# UmnitsaUltrasonic.net
KiCad netlist of a schematic drawn in EAGLE
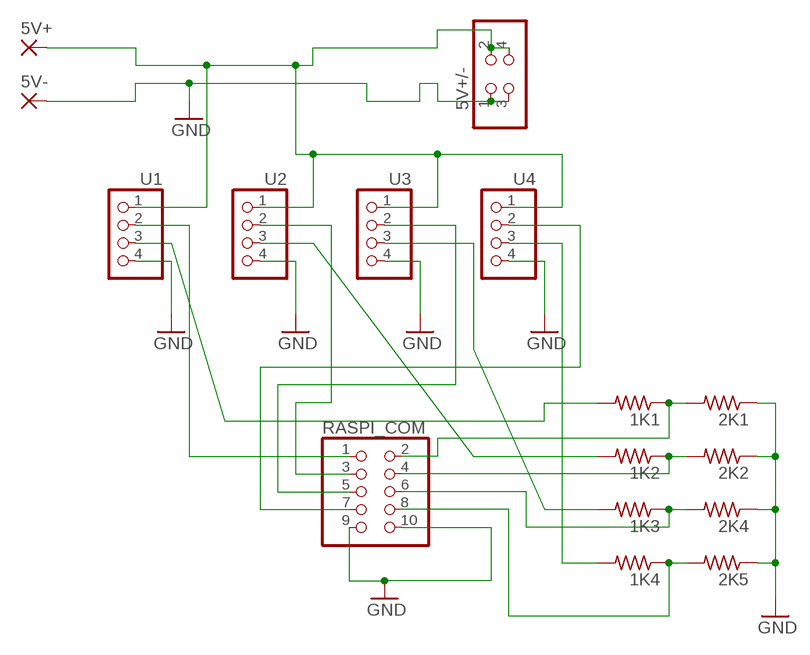
[diagram p0: schematic, sheet 1]

(export (version "E")
  (design (tool "Eeschema 10.0.6"))
  (components
    (comp (ref "1K1")
      (value "R-US_0204/7")
      (footprint "eagle-import:0204_7")
      (libsource (lib "eagle-import") (part "R-US_0204/7"))
    )
    (comp (ref "1K2")
      (value "R-US_0204/7")
      (footprint "eagle-import:0204_7")
      (libsource (lib "eagle-import") (part "R-US_0204/7"))
    )
    (comp (ref "1K3")
      (value "R-US_0204/7")
      (footprint "eagle-import:0204_7")
      (libsource (lib "eagle-import") (part "R-US_0204/7"))
    )
    (comp (ref "1K4")
      (value "R-US_0204/7")
      (footprint "eagle-import:0204_7")
      (libsource (lib "eagle-import") (part "R-US_0204/7"))
    )
    (comp (ref "2K1")
      (value "R-US_0204/7")
      (footprint "eagle-import:0204_7")
      (libsource (lib "eagle-import") (part "R-US_0204/7"))
    )
    (comp (ref "2K2")
      (value "R-US_0204/7")
      (footprint "eagle-import:0204_7")
      (libsource (lib "eagle-import") (part "R-US_0204/7"))
    )
    (comp (ref "2K4")
      (value "R-US_0204/7")
      (footprint "eagle-import:0204_7")
      (libsource (lib "eagle-import") (part "R-US_0204/7"))
    )
    (comp (ref "2K5")
      (value "R-US_0204/7")
      (footprint "eagle-import:0204_7")
      (libsource (lib "eagle-import") (part "R-US_0204/7"))
    )
    (comp (ref "5V+")
      (value "3,17/1,3")
      (footprint "eagle-import:3,17_1,3")
      (libsource (lib "eagle-import") (part "3,17/1,3"))
    )
    (comp (ref "5V+/-")
      (value "PINHD-2X2")
      (footprint "eagle-import:2X02")
      (libsource (lib "eagle-import") (part "PINHD-2X2"))
    )
    (comp (ref "5V-")
      (value "3,17/1,3")
      (footprint "eagle-import:3,17_1,3")
      (libsource (lib "eagle-import") (part "3,17/1,3"))
    )
    (comp (ref "RASPI_COM")
      (value "PINHD-2X5")
      (footprint "eagle-import:2X05")
      (libsource (lib "eagle-import") (part "PINHD-2X5"))
    )
    (comp (ref "U1")
      (value "PINHD-1X4")
      (footprint "eagle-import:1X04")
      (libsource (lib "eagle-import") (part "PINHD-1X4"))
    )
    (comp (ref "U2")
      (value "PINHD-1X4")
      (footprint "eagle-import:1X04")
      (libsource (lib "eagle-import") (part "PINHD-1X4"))
    )
    (comp (ref "U3")
      (value "PINHD-1X4")
      (footprint "eagle-import:1X04")
      (libsource (lib "eagle-import") (part "PINHD-1X4"))
    )
    (comp (ref "U4")
      (value "PINHD-1X4")
      (footprint "eagle-import:1X04")
      (libsource (lib "eagle-import") (part "PINHD-1X4"))
    )
  )
  (nets
    (net (code "1") (name "GND") (class "Default")
      (node (ref "2K1") (pin "1") (pinfunction "1_1") (pintype "passive"))
      (node (ref "2K2") (pin "1") (pinfunction "1_1") (pintype "passive"))
      (node (ref "2K4") (pin "1") (pinfunction "1_1") (pintype "passive"))
      (node (ref "2K5") (pin "1") (pinfunction "1_1") (pintype "passive"))
      (node (ref "5V+/-") (pin "1") (pinfunction "1_1") (pintype "passive"))
      (node (ref "5V+/-") (pin "3") (pinfunction "3_3") (pintype "passive"))
      (node (ref "5V-") (pin "1") (pinfunction "P_1") (pintype "passive"))
      (node (ref "RASPI_COM") (pin "10") (pinfunction "10_10") (pintype "passive"))
      (node (ref "RASPI_COM") (pin "9") (pinfunction "9_9") (pintype "passive"))
      (node (ref "U1") (pin "4") (pinfunction "4_4") (pintype "passive"))
      (node (ref "U2") (pin "4") (pinfunction "4_4") (pintype "passive"))
      (node (ref "U3") (pin "4") (pinfunction "4_4") (pintype "passive"))
      (node (ref "U4") (pin "4") (pinfunction "4_4") (pintype "passive"))
    )
    (net (code "2") (name "Net-(1K1-Pad1)") (class "Default")
      (node (ref "1K1") (pin "1") (pinfunction "1_1") (pintype "passive"))
      (node (ref "2K1") (pin "2") (pinfunction "2_2") (pintype "passive"))
      (node (ref "RASPI_COM") (pin "2") (pinfunction "2_2") (pintype "passive"))
    )
    (net (code "3") (name "Net-(1K1-Pad2)") (class "Default")
      (node (ref "1K1") (pin "2") (pinfunction "2_2") (pintype "passive"))
      (node (ref "U1") (pin "3") (pinfunction "3_3") (pintype "passive"))
    )
    (net (code "4") (name "Net-(1K2-Pad1)") (class "Default")
      (node (ref "1K2") (pin "1") (pinfunction "1_1") (pintype "passive"))
      (node (ref "2K2") (pin "2") (pinfunction "2_2") (pintype "passive"))
      (node (ref "RASPI_COM") (pin "4") (pinfunction "4_4") (pintype "passive"))
    )
    (net (code "5") (name "Net-(1K2-Pad2)") (class "Default")
      (node (ref "1K2") (pin "2") (pinfunction "2_2") (pintype "passive"))
      (node (ref "U2") (pin "3") (pinfunction "3_3") (pintype "passive"))
    )
    (net (code "6") (name "Net-(1K3-Pad1)") (class "Default")
      (node (ref "1K3") (pin "1") (pinfunction "1_1") (pintype "passive"))
      (node (ref "2K4") (pin "2") (pinfunction "2_2") (pintype "passive"))
      (node (ref "RASPI_COM") (pin "6") (pinfunction "6_6") (pintype "passive"))
    )
    (net (code "7") (name "Net-(1K3-Pad2)") (class "Default")
      (node (ref "1K3") (pin "2") (pinfunction "2_2") (pintype "passive"))
      (node (ref "U3") (pin "3") (pinfunction "3_3") (pintype "passive"))
    )
    (net (code "8") (name "Net-(1K4-Pad1)") (class "Default")
      (node (ref "1K4") (pin "1") (pinfunction "1_1") (pintype "passive"))
      (node (ref "2K5") (pin "2") (pinfunction "2_2") (pintype "passive"))
      (node (ref "RASPI_COM") (pin "8") (pinfunction "8_8") (pintype "passive"))
    )
    (net (code "9") (name "Net-(1K4-Pad2)") (class "Default")
      (node (ref "1K4") (pin "2") (pinfunction "2_2") (pintype "passive"))
      (node (ref "U4") (pin "3") (pinfunction "3_3") (pintype "passive"))
    )
    (net (code "10") (name "Net-(5V+-P)") (class "Default")
      (node (ref "5V+") (pin "1") (pinfunction "P_1") (pintype "passive"))
      (node (ref "5V+/-") (pin "2") (pinfunction "2_2") (pintype "passive"))
      (node (ref "5V+/-") (pin "4") (pinfunction "4_4") (pintype "passive"))
      (node (ref "U1") (pin "1") (pinfunction "1_1") (pintype "passive"))
      (node (ref "U2") (pin "1") (pinfunction "1_1") (pintype "passive"))
      (node (ref "U3") (pin "1") (pinfunction "1_1") (pintype "passive"))
      (node (ref "U4") (pin "1") (pinfunction "1_1") (pintype "passive"))
    )
    (net (code "11") (name "Net-(RASPI_COM-Pad1)") (class "Default")
      (node (ref "RASPI_COM") (pin "1") (pinfunction "1_1") (pintype "passive"))
      (node (ref "U1") (pin "2") (pinfunction "2_2") (pintype "passive"))
    )
    (net (code "12") (name "Net-(RASPI_COM-Pad3)") (class "Default")
      (node (ref "RASPI_COM") (pin "3") (pinfunction "3_3") (pintype "passive"))
      (node (ref "U2") (pin "2") (pinfunction "2_2") (pintype "passive"))
    )
    (net (code "13") (name "Net-(RASPI_COM-Pad5)") (class "Default")
      (node (ref "RASPI_COM") (pin "5") (pinfunction "5_5") (pintype "passive"))
      (node (ref "U3") (pin "2") (pinfunction "2_2") (pintype "passive"))
    )
    (net (code "14") (name "Net-(RASPI_COM-Pad7)") (class "Default")
      (node (ref "RASPI_COM") (pin "7") (pinfunction "7_7") (pintype "passive"))
      (node (ref "U4") (pin "2") (pinfunction "2_2") (pintype "passive"))
    )
  )
)
